# TuneIt.net
KiCad netlist of a schematic drawn in Altium Designer
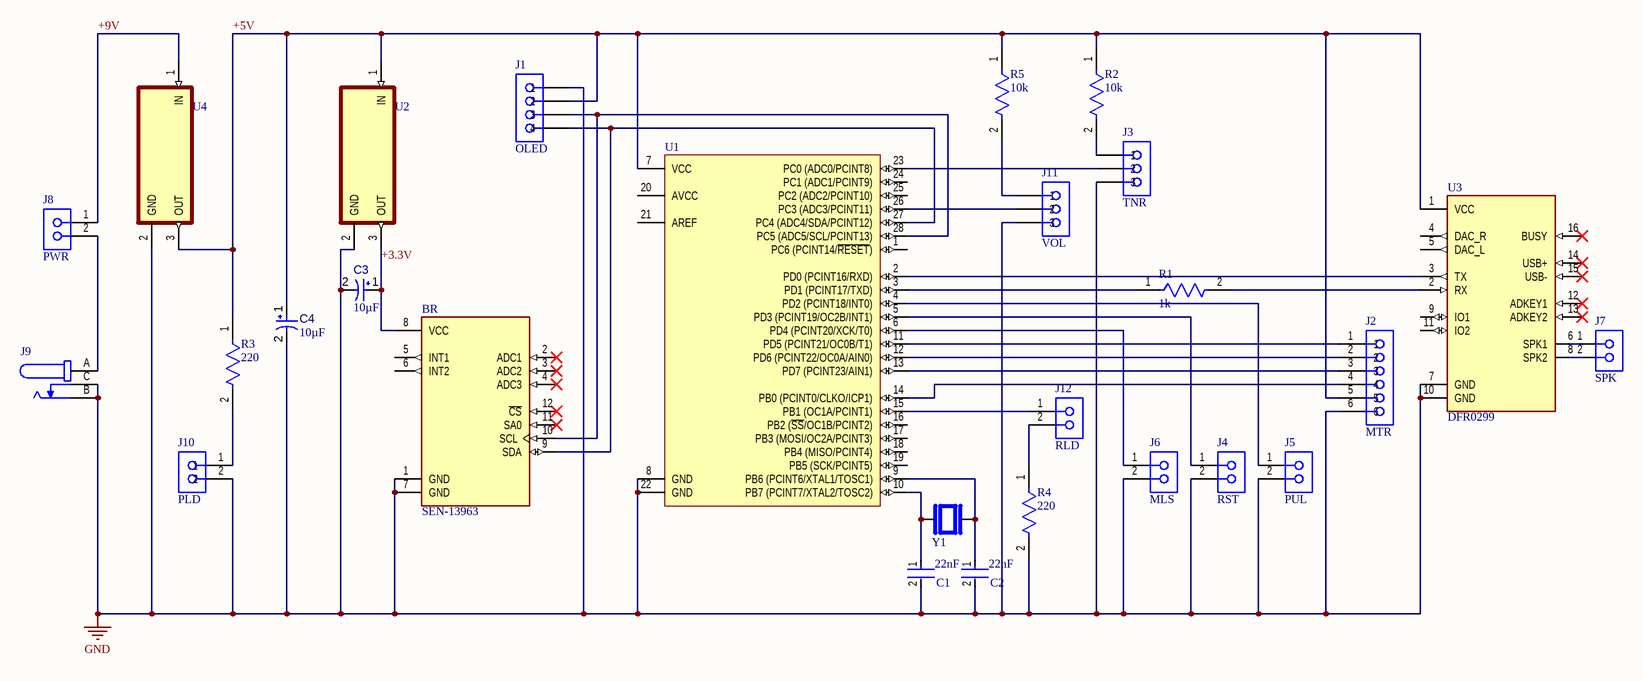
[diagram p0: TuneIt.SchDoc]

(export (version "E")
  (design (tool "Eeschema 10.0.6"))
  (components
    (comp (ref "BR")
      (value "SEN-13963")
      (footprint "SEN-13963")
      (description "LIS3DH - Accelerometer, 3 Axis Sensor Evaluation Board")
      (fields (field (name "MF") "SparkFun Electronics"))
      (libsource (lib "University of Pittsburgh") (part "SEN-13963"))
    )
    (comp (ref "C1")
      (value "22nF")
      (footprint "FP-RCE0DB-MFG")
      (description "CAP CER 10000PF 50V X7R RADIAL")
      (libsource (lib "University of Pittsburgh") (part "b4654b650e69147ec39a6b967a45e02"))
    )
    (comp (ref "C2")
      (value "22nF")
      (footprint "FP-RCE0DB-MFG")
      (description "CAP CER 10000PF 50V X7R RADIAL")
      (libsource (lib "University of Pittsburgh") (part "b4654b650e69147ec39a6b967a45e02"))
    )
    (comp (ref "C3")
      (value "10µF")
      (footprint "CAPPR55-200-1100X500X1200")
      (description "Aluminum Electrolytic Capacitor, 10 uF, +/- 20%, 50 V, -40 to 85 degC, 2-Pin THD, RoHS, Bulk")
      (fields (field (name "TOLERANCE") "20%") (field (name "MANUFACTURER") "Panasonic"))
      (libsource (lib "") (part "CAP-P-2_1"))
    )
    (comp (ref "C4")
      (value "10µF")
      (footprint "CAPPR55-200-1100X500X1200")
      (description "Aluminum Electrolytic Capacitor, 10 uF, +/- 20%, 50 V, -40 to 85 degC, 2-Pin THD, RoHS, Bulk")
      (fields (field (name "TOLERANCE") "20%") (field (name "MANUFACTURER") "Panasonic"))
      (libsource (lib "University of Pittsburgh") (part "CAP-P-2"))
    )
    (comp (ref "J1")
      (value "OLED")
      (footprint "61300411821")
      (description "WR-PHD Socket Header, THT, Vertical, pitch 2.54mm, 1 Row, 4P")
      (fields
        (field (name "MANUFACTURER") "Wurth Elektronik")
        (field (name "MANUFACTURER PART NUMBER") "61300411821")
      )
      (libsource (lib "University of Pittsburgh") (part "613004143121"))
    )
    (comp (ref "J2")
      (value "MTR")
      (footprint "61300611821")
      (description "WR-PHD Socket Header, THT, Vertical, pitch 2.54mm, 1 Row, 6P")
      (fields
        (field (name "MANUFACTURER") "Wurth Elektronik")
        (field (name "MANUFACTURER PART NUMBER") "61300611821")
      )
      (libsource (lib "University of Pittsburgh") (part "613006143121"))
    )
    (comp (ref "J3")
      (value "TNR")
      (footprint "61300311821")
      (description "WR-PHD Socket Header, THT, Vertical, pitch 2.54mm, 1 Row, 3P")
      (fields
        (field (name "MANUFACTURER") "Wurth Elektronik")
        (field (name "MANUFACTURER PART NUMBER") "61300311821")
      )
      (libsource (lib "University of Pittsburgh") (part "613003143121"))
    )
    (comp (ref "J4")
      (value "RST")
      (footprint "61300211821")
      (description "WR-PHD Socket Header, THT, Vertical, pitch 2.54mm, 1 Row, 2P")
      (fields
        (field (name "MANUFACTURER PART NUMBER") "61300211821")
        (field (name "MANUFACTURER") "Wurth Elektronik")
      )
      (libsource (lib "University of Pittsburgh") (part "613002143121"))
    )
    (comp (ref "J5")
      (value "PUL")
      (footprint "61300211821")
      (description "WR-PHD Socket Header, THT, Vertical, pitch 2.54mm, 1 Row, 2P")
      (fields
        (field (name "MANUFACTURER PART NUMBER") "61300211821")
        (field (name "MANUFACTURER") "Wurth Elektronik")
      )
      (libsource (lib "University of Pittsburgh") (part "613002143121"))
    )
    (comp (ref "J6")
      (value "MLS")
      (footprint "61300211821")
      (description "WR-PHD Socket Header, THT, Vertical, pitch 2.54mm, 1 Row, 2P")
      (fields
        (field (name "MANUFACTURER PART NUMBER") "61300211821")
        (field (name "MANUFACTURER") "Wurth Elektronik")
      )
      (libsource (lib "University of Pittsburgh") (part "613002143121"))
    )
    (comp (ref "J7")
      (value "SPK")
      (footprint "61300211821")
      (description "WR-PHD Socket Header, THT, Vertical, pitch 2.54mm, 1 Row, 2P")
      (fields
        (field (name "MANUFACTURER PART NUMBER") "61300211821")
        (field (name "MANUFACTURER") "Wurth Elektronik")
      )
      (libsource (lib "University of Pittsburgh") (part "613002143121"))
    )
    (comp (ref "J8")
      (value "PWR")
      (footprint "61300211821")
      (description "WR-PHD Socket Header, THT, Vertical, pitch 2.54mm, 1 Row, 2P")
      (fields
        (field (name "MANUFACTURER PART NUMBER") "61300211821")
        (field (name "MANUFACTURER") "Wurth Elektronik")
      )
      (libsource (lib "University of Pittsburgh") (part "613002143121"))
    )
    (comp (ref "J9")
      (value "54-00130")
      (footprint "TENSILITY_54-00130")
      (description "Connector, dc jack 5.5x2.5 mm, PCB mount, 90 degrees, silver plated, thru hole")
      (fields (field (name "MF") "Tensility International Corp"))
      (libsource (lib "University of Pittsburgh") (part "54-00130"))
    )
    (comp (ref "J10")
      (value "PLD")
      (footprint "61300211821")
      (description "WR-PHD Socket Header, THT, Vertical, pitch 2.54mm, 1 Row, 2P")
      (fields
        (field (name "MANUFACTURER PART NUMBER") "61300211821")
        (field (name "MANUFACTURER") "Wurth Elektronik")
      )
      (libsource (lib "") (part "613002143121_1"))
    )
    (comp (ref "J11")
      (value "VOL")
      (footprint "61300311821")
      (description "WR-PHD Socket Header, THT, Vertical, pitch 2.54mm, 1 Row, 3P")
      (fields
        (field (name "MANUFACTURER") "Wurth Elektronik")
        (field (name "MANUFACTURER PART NUMBER") "61300311821")
      )
      (libsource (lib "University of Pittsburgh") (part "613003143121"))
    )
    (comp (ref "J12")
      (value "RLD")
      (footprint "61300211821")
      (description "WR-PHD Socket Header, THT, Vertical, pitch 2.54mm, 1 Row, 2P")
      (fields
        (field (name "MANUFACTURER PART NUMBER") "61300211821")
        (field (name "MANUFACTURER") "Wurth Elektronik")
      )
      (libsource (lib "University of Pittsburgh") (part "613002143121"))
    )
    (comp (ref "R1")
      (value "VR37000001204JA100")
      (footprint "FP-VR37-MFG")
      (description "RES 1.2M OHM 5% 1/2W AXIAL")
      (fields (field (name "TOLERANCE") "5%") (field (name "RESISTANCE") "1k"))
      (libsource (lib "Altium Content Vault") (part "1029c3af85768c4190bb7ad29bc67b5"))
    )
    (comp (ref "R2")
      (value "VR37000001204JA100")
      (footprint "FP-VR37-MFG")
      (description "RES 1.2M OHM 5% 1/2W AXIAL")
      (fields (field (name "TOLERANCE") "5%") (field (name "RESISTANCE") "10k"))
      (libsource (lib "Altium Content Vault") (part "1029c3af85768c4190bb7ad29bc67b5"))
    )
    (comp (ref "R3")
      (value "VR37000001204JA100")
      (footprint "FP-VR37-MFG")
      (description "RES 1.2M OHM 5% 1/2W AXIAL")
      (fields (field (name "TOLERANCE") "5%") (field (name "RESISTANCE") "220"))
      (libsource (lib "Altium Content Vault") (part "1029c3af85768c4190bb7ad29bc67b5"))
    )
    (comp (ref "R4")
      (value "VR37000001204JA100")
      (footprint "FP-VR37-MFG")
      (description "RES 1.2M OHM 5% 1/2W AXIAL")
      (fields (field (name "TOLERANCE") "5%") (field (name "RESISTANCE") "220"))
      (libsource (lib "Altium Content Vault") (part "1029c3af85768c4190bb7ad29bc67b5"))
    )
    (comp (ref "R5")
      (value "VR37000001204JA100")
      (footprint "FP-VR37-MFG")
      (description "RES 1.2M OHM 5% 1/2W AXIAL")
      (fields (field (name "TOLERANCE") "5%") (field (name "RESISTANCE") "10k"))
      (libsource (lib "Altium Content Vault") (part "1029c3af85768c4190bb7ad29bc67b5"))
    )
    (comp (ref "U1")
      (value "ATMEGA328P-PU")
      (footprint "ATML-28P3")
      (fields (field (name "MANUFACTURER") "Atmel"))
      (libsource (lib "University of Pittsburgh") (part "MC-8B-ATM48-IL28"))
    )
    (comp (ref "U2")
      (value "LM2937ET-3.3/NOPB")
      (footprint "TO254P1054X470X1955-3")
      (libsource (lib "University of Pittsburgh") (part "LM2937ET-3.3/NOPB"))
    )
    (comp (ref "U3")
      (value "DFR0299")
      (footprint "MODULE_DFR0299")
      (description "- MP3 Player Audio Arduino Platform Evaluation Expansion Board")
      (fields (field (name "MF") "DFRobot"))
      (libsource (lib "University of Pittsburgh") (part "DFR0299"))
    )
    (comp (ref "U4")
      (value "LM2937ET-3.3/NOPB")
      (footprint "TO254P1054X470X1955-3")
      (libsource (lib "University of Pittsburgh") (part "LM2937ET-3.3/NOPB"))
    )
    (comp (ref "Y1")
      (value "ABL-16.000MHz-B1U-T")
      (footprint "XTAL_HC49P488W46L1150T500H350")
      (description "16 MHz Â±10ppm Crystal 18pF 40 Ohms HC-49/US")
      (fields (field (name "MF") "Abracon LLC") (field (name "MP") "ABL-16.000MHz-B1U"))
      (libsource (lib "University of Pittsburgh") (part "ABL-16.000MHz-B1U-T"))
    )
  )
  (nets
    (net (code "1") (name "/+3.3V") (class "Default")
      (node (ref "BR") (pin "8") (pinfunction "VCC_8") (pintype "power_in"))
      (node (ref "C3") (pin "1") (pinfunction "1_1") (pintype "passive"))
      (node (ref "U2") (pin "3") (pinfunction "OUT_3") (pintype "output"))
    )
    (net (code "2") (name "/+5V") (class "Default")
      (node (ref "C4") (pin "1") (pinfunction "1_1") (pintype "passive"))
      (node (ref "J1") (pin "2") (pinfunction "2_2") (pintype "passive"))
      (node (ref "J2") (pin "5") (pinfunction "5_5") (pintype "passive"))
      (node (ref "R2") (pin "1") (pinfunction "1_1") (pintype "passive"))
      (node (ref "R3") (pin "1") (pinfunction "1_1") (pintype "passive"))
      (node (ref "R5") (pin "1") (pinfunction "1_1") (pintype "passive"))
      (node (ref "U1") (pin "7") (pinfunction "VCC_7") (pintype "power_in"))
      (node (ref "U2") (pin "1") (pinfunction "IN_1") (pintype "input"))
      (node (ref "U3") (pin "1") (pinfunction "VCC_1") (pintype "power_in"))
      (node (ref "U4") (pin "3") (pinfunction "OUT_3") (pintype "output"))
    )
    (net (code "3") (name "/+9V") (class "Default")
      (node (ref "J8") (pin "1") (pinfunction "1_1") (pintype "passive"))
      (node (ref "U4") (pin "1") (pinfunction "IN_1") (pintype "input"))
    )
    (net (code "4") (name "GND") (class "Default")
      (node (ref "BR") (pin "1") (pinfunction "GND_1") (pintype "power_in"))
      (node (ref "BR") (pin "7") (pinfunction "GND_7") (pintype "power_in"))
      (node (ref "C1") (pin "2") (pinfunction "2_2") (pintype "passive"))
      (node (ref "C2") (pin "2") (pinfunction "2_2") (pintype "passive"))
      (node (ref "C3") (pin "2") (pinfunction "2_2") (pintype "passive"))
      (node (ref "C4") (pin "2") (pinfunction "2_2") (pintype "passive"))
      (node (ref "J1") (pin "1") (pinfunction "1_1") (pintype "passive"))
      (node (ref "J10") (pin "2") (pinfunction "2_2") (pintype "passive"))
      (node (ref "J11") (pin "3") (pinfunction "3_3") (pintype "passive"))
      (node (ref "J2") (pin "6") (pinfunction "6_6") (pintype "passive"))
      (node (ref "J3") (pin "3") (pinfunction "3_3") (pintype "passive"))
      (node (ref "J4") (pin "2") (pinfunction "2_2") (pintype "passive"))
      (node (ref "J5") (pin "2") (pinfunction "2_2") (pintype "passive"))
      (node (ref "J6") (pin "2") (pinfunction "2_2") (pintype "passive"))
      (node (ref "J9") (pin "B") (pinfunction "B_B") (pintype "passive"))
      (node (ref "J9") (pin "C") (pinfunction "C_C") (pintype "passive"))
      (node (ref "R4") (pin "2") (pinfunction "2_2") (pintype "passive"))
      (node (ref "U1") (pin "22") (pinfunction "GND_22") (pintype "power_in"))
      (node (ref "U1") (pin "8") (pinfunction "GND_8") (pintype "power_in"))
      (node (ref "U2") (pin "2") (pinfunction "GND_2") (pintype "power_in"))
      (node (ref "U3") (pin "10") (pinfunction "GND_10") (pintype "power_in"))
      (node (ref "U3") (pin "7") (pinfunction "GND_7") (pintype "power_in"))
      (node (ref "U4") (pin "2") (pinfunction "GND_2") (pintype "power_in"))
    )
    (net (code "5") (name "Net-(BR-SCL)") (class "Default")
      (node (ref "BR") (pin "10") (pinfunction "SCL_10") (pintype "input"))
      (node (ref "J1") (pin "3") (pinfunction "3_3") (pintype "passive"))
      (node (ref "U1") (pin "28") (pinfunction "PC5_(ADC5/SCL/PCINT13)_28") (pintype "bidirectional"))
    )
    (net (code "6") (name "Net-(BR-SDA)") (class "Default")
      (node (ref "BR") (pin "9") (pinfunction "SDA_9") (pintype "bidirectional"))
      (node (ref "J1") (pin "4") (pinfunction "4_4") (pintype "passive"))
      (node (ref "U1") (pin "27") (pinfunction "PC4_(ADC4/SDA/PCINT12)_27") (pintype "bidirectional"))
    )
    (net (code "7") (name "Net-(J3-Pad1)") (class "Default")
      (node (ref "J3") (pin "1") (pinfunction "1_1") (pintype "passive"))
      (node (ref "R2") (pin "2") (pinfunction "2_2") (pintype "passive"))
    )
    (net (code "8") (name "Net-(J8-Pad2)") (class "Default")
      (node (ref "J8") (pin "2") (pinfunction "2_2") (pintype "passive"))
      (node (ref "J9") (pin "A") (pinfunction "A_A") (pintype "passive"))
    )
    (net (code "9") (name "Net-(J10-Pad1)") (class "Default")
      (node (ref "J10") (pin "1") (pinfunction "1_1") (pintype "passive"))
      (node (ref "R3") (pin "2") (pinfunction "2_2") (pintype "passive"))
    )
    (net (code "10") (name "Net-(J11-Pad1)") (class "Default")
      (node (ref "J11") (pin "1") (pinfunction "1_1") (pintype "passive"))
      (node (ref "R5") (pin "2") (pinfunction "2_2") (pintype "passive"))
    )
    (net (code "11") (name "Net-(J12-Pad2)") (class "Default")
      (node (ref "J12") (pin "2") (pinfunction "2_2") (pintype "passive"))
      (node (ref "R4") (pin "1") (pinfunction "1_1") (pintype "passive"))
    )
    (net (code "12") (name "Net-(U1-PB0_(PCINT0{slash}CLKO{slash}ICP1))") (class "Default")
      (node (ref "J2") (pin "4") (pinfunction "4_4") (pintype "passive"))
      (node (ref "U1") (pin "14") (pinfunction "PB0_(PCINT0/CLKO/ICP1)_14") (pintype "bidirectional"))
    )
    (net (code "13") (name "Net-(U1-PB1_(OC1A{slash}PCINT1))") (class "Default")
      (node (ref "J12") (pin "1") (pinfunction "1_1") (pintype "passive"))
      (node (ref "U1") (pin "15") (pinfunction "PB1_(OC1A/PCINT1)_15") (pintype "bidirectional"))
    )
    (net (code "14") (name "Net-(U1-PB6_(PCINT6{slash}XTAL1{slash}TOSC1))") (class "Default")
      (node (ref "C2") (pin "1") (pinfunction "1_1") (pintype "passive"))
      (node (ref "U1") (pin "9") (pinfunction "PB6_(PCINT6/XTAL1/TOSC1)_9") (pintype "bidirectional"))
      (node (ref "Y1") (pin "1") (pinfunction "1_1") (pintype "passive"))
    )
    (net (code "15") (name "Net-(U1-PB7_(PCINT7{slash}XTAL2{slash}TOSC2))") (class "Default")
      (node (ref "C1") (pin "1") (pinfunction "1_1") (pintype "passive"))
      (node (ref "U1") (pin "10") (pinfunction "PB7_(PCINT7/XTAL2/TOSC2)_10") (pintype "bidirectional"))
      (node (ref "Y1") (pin "2") (pinfunction "2_2") (pintype "passive"))
    )
    (net (code "16") (name "Net-(U1-PC0_(ADC0{slash}PCINT8))") (class "Default")
      (node (ref "J3") (pin "2") (pinfunction "2_2") (pintype "passive"))
      (node (ref "U1") (pin "23") (pinfunction "PC0_(ADC0/PCINT8)_23") (pintype "bidirectional"))
    )
    (net (code "17") (name "Net-(U1-PC3_(ADC3{slash}PCINT11))") (class "Default")
      (node (ref "J11") (pin "2") (pinfunction "2_2") (pintype "passive"))
      (node (ref "U1") (pin "26") (pinfunction "PC3_(ADC3/PCINT11)_26") (pintype "bidirectional"))
    )
    (net (code "18") (name "Net-(U1-PD0_(PCINT16{slash}RXD))") (class "Default")
      (node (ref "U1") (pin "2") (pinfunction "PD0_(PCINT16/RXD)_2") (pintype "bidirectional"))
      (node (ref "U3") (pin "3") (pinfunction "TX_3") (pintype "output"))
    )
    (net (code "19") (name "Net-(U1-PD1_(PCINT17{slash}TXD))") (class "Default")
      (node (ref "R1") (pin "1") (pinfunction "1_1") (pintype "passive"))
      (node (ref "U1") (pin "3") (pinfunction "PD1_(PCINT17/TXD)_3") (pintype "bidirectional"))
    )
    (net (code "20") (name "Net-(U1-PD2_(PCINT18{slash}INT0))") (class "Default")
      (node (ref "J5") (pin "1") (pinfunction "1_1") (pintype "passive"))
      (node (ref "U1") (pin "4") (pinfunction "PD2_(PCINT18/INT0)_4") (pintype "bidirectional"))
    )
    (net (code "21") (name "Net-(U1-PD3_(PCINT19{slash}OC2B{slash}INT1))") (class "Default")
      (node (ref "J4") (pin "1") (pinfunction "1_1") (pintype "passive"))
      (node (ref "U1") (pin "5") (pinfunction "PD3_(PCINT19/OC2B/INT1)_5") (pintype "bidirectional"))
    )
    (net (code "22") (name "Net-(U1-PD4_(PCINT20{slash}XCK{slash}T0))") (class "Default")
      (node (ref "J6") (pin "1") (pinfunction "1_1") (pintype "passive"))
      (node (ref "U1") (pin "6") (pinfunction "PD4_(PCINT20/XCK/T0)_6") (pintype "bidirectional"))
    )
    (net (code "23") (name "Net-(U1-PD5_(PCINT21{slash}OC0B{slash}T1))") (class "Default")
      (node (ref "J2") (pin "1") (pinfunction "1_1") (pintype "passive"))
      (node (ref "U1") (pin "11") (pinfunction "PD5_(PCINT21/OC0B/T1)_11") (pintype "bidirectional"))
    )
    (net (code "24") (name "Net-(U1-PD6_(PCINT22{slash}OC0A{slash}AIN0))") (class "Default")
      (node (ref "J2") (pin "2") (pinfunction "2_2") (pintype "passive"))
      (node (ref "U1") (pin "12") (pinfunction "PD6_(PCINT22/OC0A/AIN0)_12") (pintype "bidirectional"))
    )
    (net (code "25") (name "Net-(U1-PD7_(PCINT23{slash}AIN1))") (class "Default")
      (node (ref "J2") (pin "3") (pinfunction "3_3") (pintype "passive"))
      (node (ref "U1") (pin "13") (pinfunction "PD7_(PCINT23/AIN1)_13") (pintype "bidirectional"))
    )
    (net (code "26") (name "Net-(U3-RX)") (class "Default")
      (node (ref "R1") (pin "2") (pinfunction "2_2") (pintype "passive"))
      (node (ref "U3") (pin "2") (pinfunction "RX_2") (pintype "input"))
    )
    (net (code "27") (name "Net-(U3-SPK1)") (class "Default")
      (node (ref "J7") (pin "1") (pinfunction "1_1") (pintype "passive"))
      (node (ref "U3") (pin "6") (pinfunction "SPK1_6") (pintype "passive"))
    )
    (net (code "28") (name "Net-(U3-SPK2)") (class "Default")
      (node (ref "J7") (pin "2") (pinfunction "2_2") (pintype "passive"))
      (node (ref "U3") (pin "8") (pinfunction "SPK2_8") (pintype "passive"))
    )
    (net (code "29") (name "unconnected-(BR-ADC1-Pad2)") (class "Default")
      (node (ref "BR") (pin "2") (pinfunction "ADC1_2") (pintype "input+no_connect"))
    )
    (net (code "30") (name "unconnected-(BR-ADC2-Pad3)") (class "Default")
      (node (ref "BR") (pin "3") (pinfunction "ADC2_3") (pintype "input+no_connect"))
    )
    (net (code "31") (name "unconnected-(BR-ADC3-Pad4)") (class "Default")
      (node (ref "BR") (pin "4") (pinfunction "ADC3_4") (pintype "input+no_connect"))
    )
    (net (code "32") (name "unconnected-(BR-INT1-Pad5)") (class "Default")
      (node (ref "BR") (pin "5") (pinfunction "INT1_5") (pintype "output"))
    )
    (net (code "33") (name "unconnected-(BR-INT2-Pad6)") (class "Default")
      (node (ref "BR") (pin "6") (pinfunction "INT2_6") (pintype "output"))
    )
    (net (code "34") (name "unconnected-(BR-SA0-Pad11)") (class "Default")
      (node (ref "BR") (pin "11") (pinfunction "SA0_11") (pintype "input+no_connect"))
    )
    (net (code "35") (name "unconnected-(BR-~{CS}-Pad12)") (class "Default")
      (node (ref "BR") (pin "12") (pinfunction "~{CS}_12") (pintype "input+no_connect"))
    )
    (net (code "36") (name "unconnected-(U1-AREF-Pad21)") (class "Default")
      (node (ref "U1") (pin "21") (pinfunction "AREF_21") (pintype "power_in"))
    )
    (net (code "37") (name "unconnected-(U1-AVCC-Pad20)") (class "Default")
      (node (ref "U1") (pin "20") (pinfunction "AVCC_20") (pintype "power_in"))
    )
    (net (code "38") (name "unconnected-(U1-PB2_(~{SS}{slash}OC1B{slash}PCINT2)-Pad16)") (class "Default")
      (node (ref "U1") (pin "16") (pinfunction "PB2_(~{SS}/OC1B/PCINT2)_16") (pintype "bidirectional"))
    )
    (net (code "39") (name "unconnected-(U1-PB3_(MOSI{slash}OC2A{slash}PCINT3)-Pad17)") (class "Default")
      (node (ref "U1") (pin "17") (pinfunction "PB3_(MOSI/OC2A/PCINT3)_17") (pintype "bidirectional"))
    )
    (net (code "40") (name "unconnected-(U1-PB4_(MISO{slash}PCINT4)-Pad18)") (class "Default")
      (node (ref "U1") (pin "18") (pinfunction "PB4_(MISO/PCINT4)_18") (pintype "bidirectional"))
    )
    (net (code "41") (name "unconnected-(U1-PB5_(SCK{slash}PCINT5)-Pad19)") (class "Default")
      (node (ref "U1") (pin "19") (pinfunction "PB5_(SCK/PCINT5)_19") (pintype "bidirectional"))
    )
    (net (code "42") (name "unconnected-(U1-PC1_(ADC1{slash}PCINT9)-Pad24)") (class "Default")
      (node (ref "U1") (pin "24") (pinfunction "PC1_(ADC1/PCINT9)_24") (pintype "bidirectional"))
    )
    (net (code "43") (name "unconnected-(U1-PC2_(ADC2{slash}PCINT10)-Pad25)") (class "Default")
      (node (ref "U1") (pin "25") (pinfunction "PC2_(ADC2/PCINT10)_25") (pintype "bidirectional"))
    )
    (net (code "44") (name "unconnected-(U1-PC6_(PCINT14{slash}~{RESET})-Pad1)") (class "Default")
      (node (ref "U1") (pin "1") (pinfunction "PC6_(PCINT14/~{RESET})_1") (pintype "bidirectional"))
    )
    (net (code "45") (name "unconnected-(U3-ADKEY1-Pad12)") (class "Default")
      (node (ref "U3") (pin "12") (pinfunction "ADKEY1_12") (pintype "input+no_connect"))
    )
    (net (code "46") (name "unconnected-(U3-ADKEY2-Pad13)") (class "Default")
      (node (ref "U3") (pin "13") (pinfunction "ADKEY2_13") (pintype "input+no_connect"))
    )
    (net (code "47") (name "unconnected-(U3-BUSY-Pad16)") (class "Default")
      (node (ref "U3") (pin "16") (pinfunction "BUSY_16") (pintype "input+no_connect"))
    )
    (net (code "48") (name "unconnected-(U3-DAC_L-Pad5)") (class "Default")
      (node (ref "U3") (pin "5") (pinfunction "DAC_L_5") (pintype "output"))
    )
    (net (code "49") (name "unconnected-(U3-DAC_R-Pad4)") (class "Default")
      (node (ref "U3") (pin "4") (pinfunction "DAC_R_4") (pintype "output"))
    )
    (net (code "50") (name "unconnected-(U3-IO1-Pad9)") (class "Default")
      (node (ref "U3") (pin "9") (pinfunction "IO1_9") (pintype "bidirectional"))
    )
    (net (code "51") (name "unconnected-(U3-IO2-Pad11)") (class "Default")
      (node (ref "U3") (pin "11") (pinfunction "IO2_11") (pintype "bidirectional"))
    )
    (net (code "52") (name "unconnected-(U3-USB+-Pad14)") (class "Default")
      (node (ref "U3") (pin "14") (pinfunction "USB+_14") (pintype "input+no_connect"))
    )
    (net (code "53") (name "unconnected-(U3-USB--Pad15)") (class "Default")
      (node (ref "U3") (pin "15") (pinfunction "USB-_15") (pintype "input+no_connect"))
    )
  )
)
